# ledFire.net
KiCad netlist of a schematic drawn in EAGLE
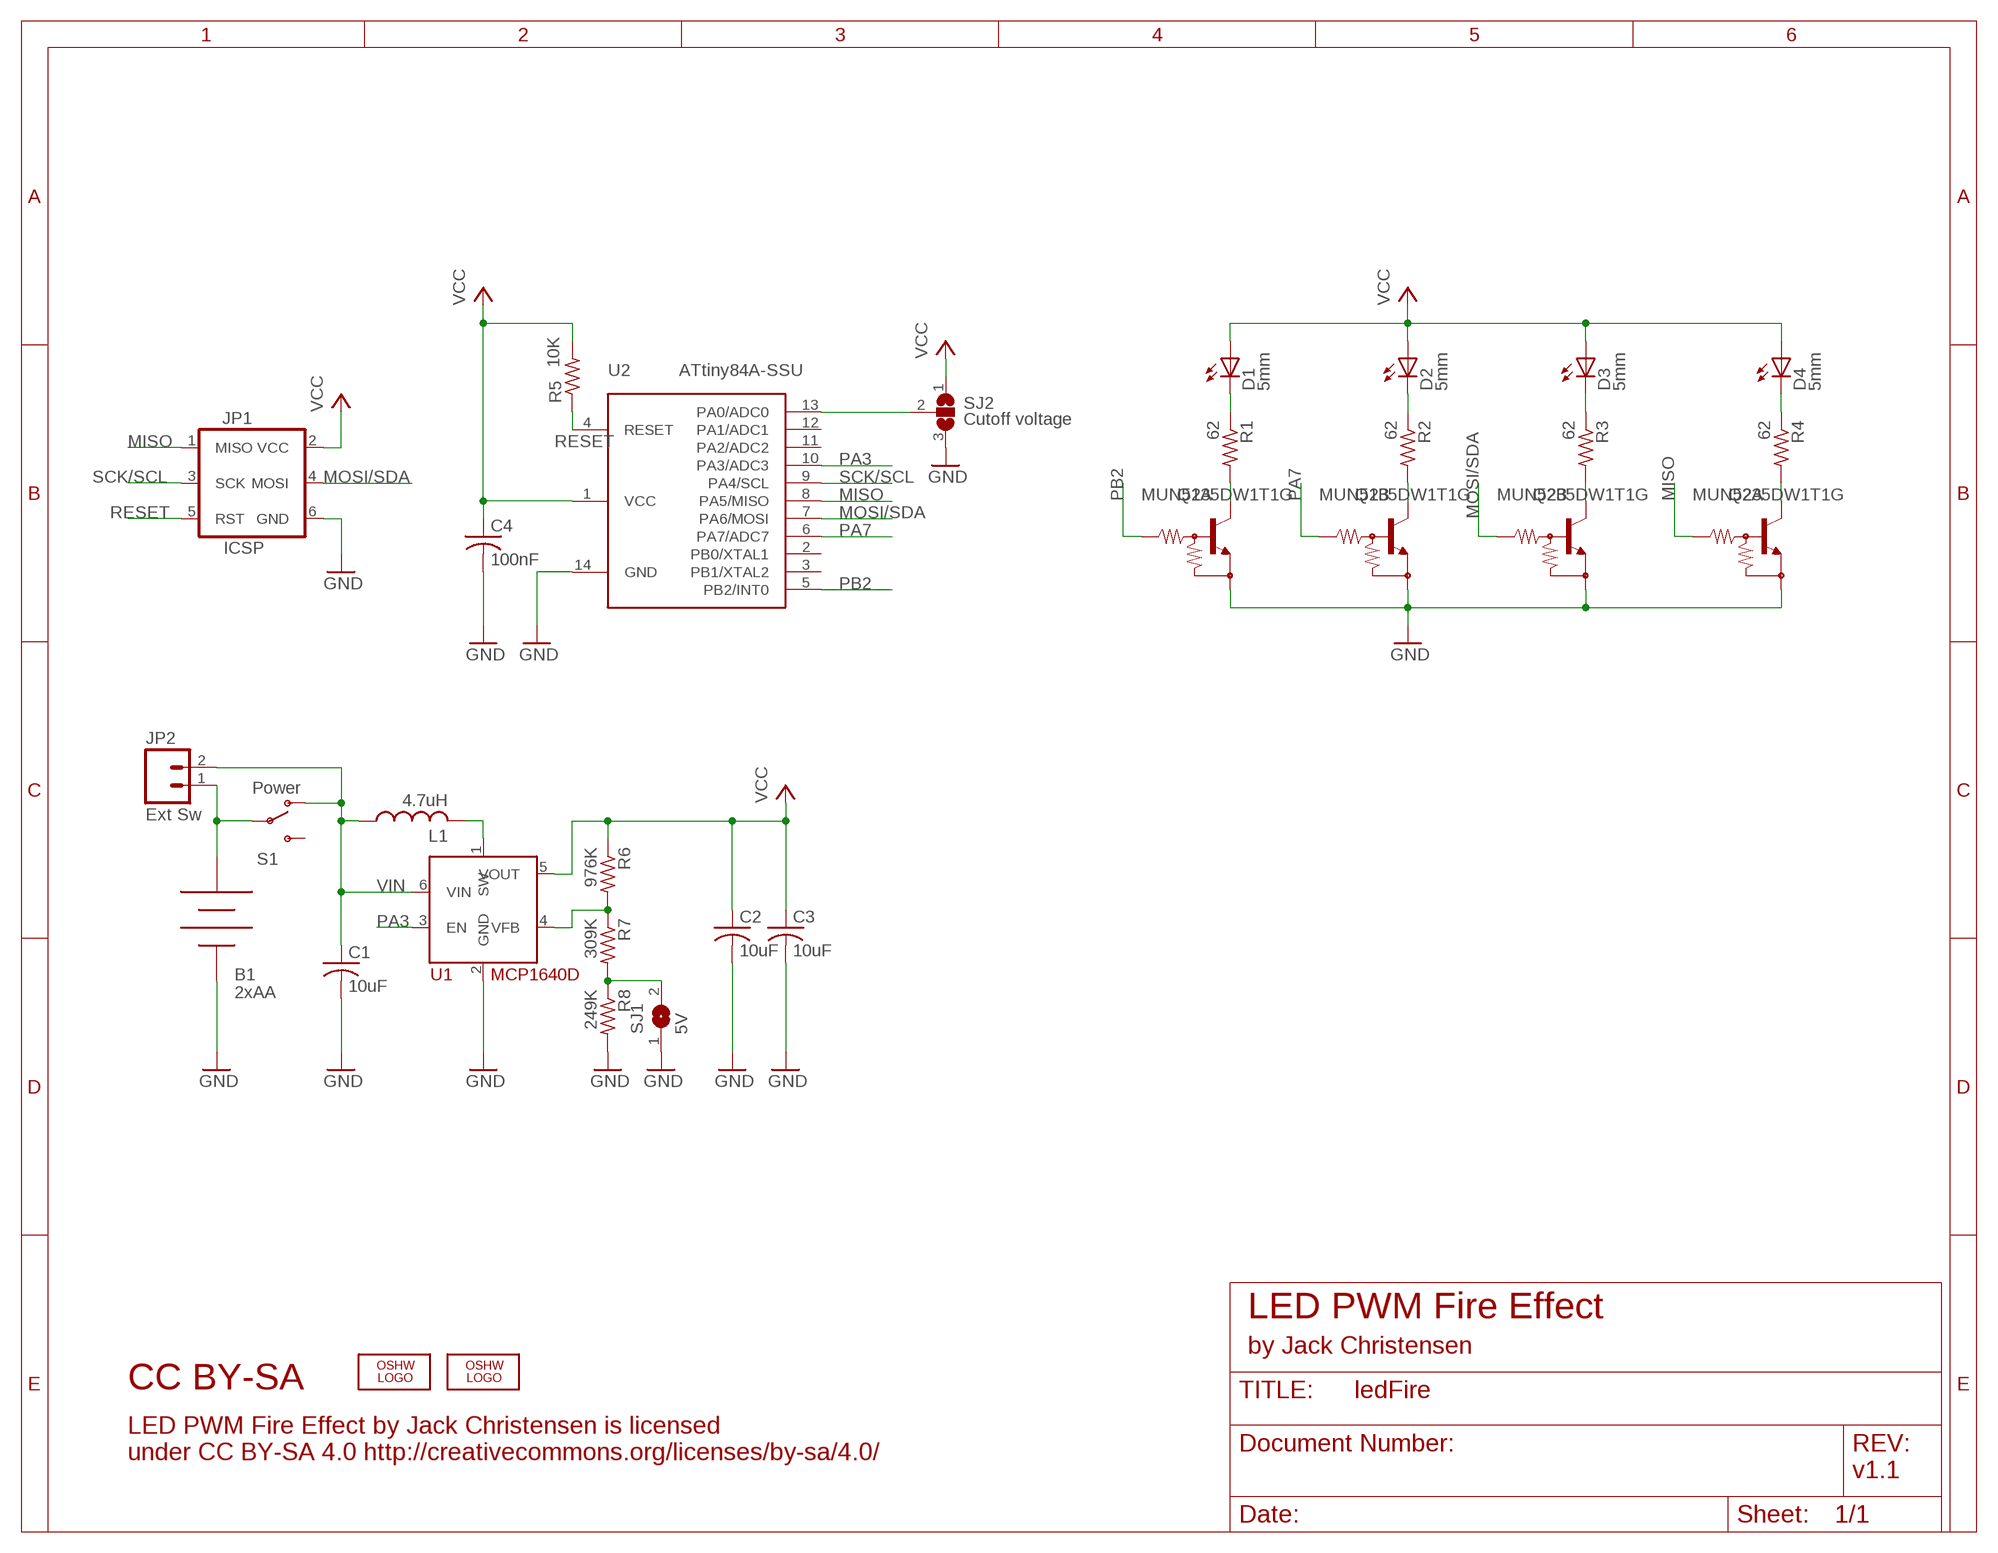
[diagram p0: schematic, sheet 1]

(export (version "E")
  (design (tool "Eeschema 10.0.6"))
  (components
    (comp (ref "B1")
      (value "2xAA")
      (footprint "eagle-import:KEYSTONE-2462-NO-HOLES")
      (libsource (lib "eagle-import") (part "BATTERY-2AANOHOLES"))
    )
    (comp (ref "C1")
      (value "10uF")
      (footprint "eagle-import:M0805")
      (libsource (lib "eagle-import") (part "C-USM0805"))
    )
    (comp (ref "C2")
      (value "10uF")
      (footprint "eagle-import:M0805")
      (libsource (lib "eagle-import") (part "C-USM0805"))
    )
    (comp (ref "C3")
      (value "10uF")
      (footprint "eagle-import:M0805")
      (libsource (lib "eagle-import") (part "C-USM0805"))
    )
    (comp (ref "C4")
      (value "100nF")
      (footprint "eagle-import:M0805")
      (libsource (lib "eagle-import") (part "C-USM0805"))
    )
    (comp (ref "D1")
      (value "5mm")
      (footprint "eagle-import:LED5MM")
      (libsource (lib "eagle-import") (part "LED5MM"))
    )
    (comp (ref "D2")
      (value "5mm")
      (footprint "eagle-import:LED5MM")
      (libsource (lib "eagle-import") (part "LED5MM"))
    )
    (comp (ref "D3")
      (value "5mm")
      (footprint "eagle-import:LED5MM")
      (libsource (lib "eagle-import") (part "LED5MM"))
    )
    (comp (ref "D4")
      (value "5mm")
      (footprint "eagle-import:LED5MM")
      (libsource (lib "eagle-import") (part "LED5MM"))
    )
    (comp (ref "JP1")
      (value "ICSP")
      (footprint "eagle-import:2X3_LOCK")
      (libsource (lib "eagle-import") (part "AVR_SPI_PRG_62X3_LOCK"))
    )
    (comp (ref "JP2")
      (value "Ext Sw")
      (footprint "eagle-import:1X02_LONGPADS")
      (libsource (lib "eagle-import") (part "M02"))
    )
    (comp (ref "L1")
      (value "4.7uH")
      (footprint "eagle-import:NRS5020")
      (libsource (lib "eagle-import") (part "INDUCTORNRS5020"))
    )
    (comp (ref "LOGO1")
      (value "OSHW_LOGO_8MILX0100-NT")
      (footprint "eagle-import:OSHW_8X100_NOTEXT")
      (libsource (lib "eagle-import") (part "OSHW_LOGO_8MILX0100-NT"))
    )
    (comp (ref "LOGO2")
      (value "OSHW_LOGO_8MILX0100-NT")
      (footprint "eagle-import:OSHW_8X100_NOTEXT")
      (libsource (lib "eagle-import") (part "OSHW_LOGO_8MILX0100-NT"))
    )
    (comp (ref "Q1")
      (value "MUN5235DW1T1G")
      (footprint "eagle-import:SOT363_PHILIPS")
      (libsource (lib "eagle-import") (part "MUN52XXSOT363"))
    )
    (comp (ref "Q2")
      (value "MUN5235DW1T1G")
      (footprint "eagle-import:SOT363_PHILIPS")
      (libsource (lib "eagle-import") (part "MUN52XXSOT363"))
    )
    (comp (ref "R1")
      (value "62")
      (footprint "eagle-import:M0805")
      (libsource (lib "eagle-import") (part "R-US_M0805"))
    )
    (comp (ref "R2")
      (value "62")
      (footprint "eagle-import:M0805")
      (libsource (lib "eagle-import") (part "R-US_M0805"))
    )
    (comp (ref "R3")
      (value "62")
      (footprint "eagle-import:M0805")
      (libsource (lib "eagle-import") (part "R-US_M0805"))
    )
    (comp (ref "R4")
      (value "62")
      (footprint "eagle-import:M0805")
      (libsource (lib "eagle-import") (part "R-US_M0805"))
    )
    (comp (ref "R5")
      (value "10K")
      (footprint "eagle-import:M0805")
      (libsource (lib "eagle-import") (part "R-US_M0805"))
    )
    (comp (ref "R6")
      (value "976K")
      (footprint "eagle-import:M0805")
      (libsource (lib "eagle-import") (part "R-US_M0805"))
    )
    (comp (ref "R7")
      (value "309K")
      (footprint "eagle-import:M0805")
      (libsource (lib "eagle-import") (part "R-US_M0805"))
    )
    (comp (ref "R8")
      (value "249K")
      (footprint "eagle-import:M0805")
      (libsource (lib "eagle-import") (part "R-US_M0805"))
    )
    (comp (ref "S1")
      (value "Power")
      (footprint "eagle-import:SWITCH-SPDT-SMD")
      (libsource (lib "eagle-import") (part "SWITCH-SPSTSMD2"))
    )
    (comp (ref "SJ1") (value "5V") (footprint "eagle-import:SJ") (libsource (lib "eagle-import") (part "SJ")))
    (comp (ref "SJ2")
      (value "Cutoff voltage")
      (footprint "eagle-import:SJ_2")
      (libsource (lib "eagle-import") (part "SJ2W"))
    )
    (comp (ref "U1")
      (value "MCP1640D")
      (footprint "eagle-import:SOT23-6")
      (libsource (lib "eagle-import") (part "MCP1640"))
    )
    (comp (ref "U2")
      (value "ATtiny84A-SSU")
      (footprint "eagle-import:SO14")
      (libsource (lib "eagle-import") (part "ATTINYX4SO14"))
    )
  )
  (nets
    (net (code "1") (name "/MISO") (class "Default")
      (node (ref "JP1") (pin "1") (pinfunction "MISO_1") (pintype "passive"))
      (node (ref "Q2") (pin "5") (pinfunction "B_5") (pintype "passive"))
      (node (ref "U2") (pin "8") (pinfunction "PA5/MISO_8") (pintype "bidirectional"))
    )
    (net (code "2") (name "/MOSI{slash}SDA") (class "Default")
      (node (ref "JP1") (pin "4") (pinfunction "MOSI_4") (pintype "passive"))
      (node (ref "Q2") (pin "2") (pinfunction "B_2") (pintype "passive"))
      (node (ref "U2") (pin "7") (pinfunction "PA6/MOSI_7") (pintype "bidirectional"))
    )
    (net (code "3") (name "/PA3") (class "Default")
      (node (ref "U1") (pin "3") (pinfunction "EN_3") (pintype "passive"))
      (node (ref "U2") (pin "10") (pinfunction "PA3/ADC3_10") (pintype "bidirectional"))
    )
    (net (code "4") (name "/PA7") (class "Default")
      (node (ref "Q1") (pin "2") (pinfunction "B_2") (pintype "passive"))
      (node (ref "U2") (pin "6") (pinfunction "PA7/ADC7_6") (pintype "bidirectional"))
    )
    (net (code "5") (name "/PB2") (class "Default")
      (node (ref "Q1") (pin "5") (pinfunction "B_5") (pintype "passive"))
      (node (ref "U2") (pin "5") (pinfunction "PB2/INT0_5") (pintype "bidirectional"))
    )
    (net (code "6") (name "/RESET") (class "Default")
      (node (ref "JP1") (pin "5") (pinfunction "RST_5") (pintype "passive"))
      (node (ref "R5") (pin "1") (pinfunction "1_1") (pintype "passive"))
      (node (ref "U2") (pin "4") (pinfunction "RESET_4") (pintype "bidirectional"))
    )
    (net (code "7") (name "/SCK{slash}SCL") (class "Default")
      (node (ref "JP1") (pin "3") (pinfunction "SCK_3") (pintype "passive"))
      (node (ref "U2") (pin "9") (pinfunction "PA4/SCL_9") (pintype "bidirectional"))
    )
    (net (code "8") (name "/VIN") (class "Default")
      (node (ref "C1") (pin "1") (pinfunction "1_1") (pintype "passive"))
      (node (ref "JP2") (pin "2") (pinfunction "2_2") (pintype "passive"))
      (node (ref "L1") (pin "P$1") (pinfunction "1_P$1") (pintype "passive"))
      (node (ref "S1") (pin "1") (pinfunction "O_1") (pintype "passive"))
      (node (ref "U1") (pin "6") (pinfunction "VIN_6") (pintype "passive"))
    )
    (net (code "9") (name "GND") (class "Default")
      (node (ref "B1") (pin "NEG") (pinfunction "NEG_NEG") (pintype "bidirectional"))
      (node (ref "C1") (pin "2") (pinfunction "2_2") (pintype "passive"))
      (node (ref "C2") (pin "2") (pinfunction "2_2") (pintype "passive"))
      (node (ref "C3") (pin "2") (pinfunction "2_2") (pintype "passive"))
      (node (ref "C4") (pin "2") (pinfunction "2_2") (pintype "passive"))
      (node (ref "JP1") (pin "6") (pinfunction "GND_6") (pintype "passive"))
      (node (ref "Q1") (pin "1") (pinfunction "E_1") (pintype "passive"))
      (node (ref "Q1") (pin "4") (pinfunction "E_4") (pintype "passive"))
      (node (ref "Q2") (pin "1") (pinfunction "E_1") (pintype "passive"))
      (node (ref "Q2") (pin "4") (pinfunction "E_4") (pintype "passive"))
      (node (ref "R8") (pin "2") (pinfunction "2_2") (pintype "passive"))
      (node (ref "SJ1") (pin "1") (pinfunction "1_1") (pintype "passive"))
      (node (ref "SJ2") (pin "3") (pinfunction "3_3") (pintype "passive"))
      (node (ref "U1") (pin "2") (pinfunction "GND_2") (pintype "passive"))
      (node (ref "U2") (pin "14") (pinfunction "GND_14") (pintype "bidirectional"))
    )
    (net (code "10") (name "Net-(D1-C)") (class "Default")
      (node (ref "D1") (pin "K") (pinfunction "C_K") (pintype "passive"))
      (node (ref "R1") (pin "1") (pinfunction "1_1") (pintype "passive"))
    )
    (net (code "11") (name "Net-(D2-C)") (class "Default")
      (node (ref "D2") (pin "K") (pinfunction "C_K") (pintype "passive"))
      (node (ref "R2") (pin "1") (pinfunction "1_1") (pintype "passive"))
    )
    (net (code "12") (name "Net-(D3-C)") (class "Default")
      (node (ref "D3") (pin "K") (pinfunction "C_K") (pintype "passive"))
      (node (ref "R3") (pin "1") (pinfunction "1_1") (pintype "passive"))
    )
    (net (code "13") (name "Net-(D4-C)") (class "Default")
      (node (ref "D4") (pin "K") (pinfunction "C_K") (pintype "passive"))
      (node (ref "R4") (pin "1") (pinfunction "1_1") (pintype "passive"))
    )
    (net (code "14") (name "Net-(L1-2)") (class "Default")
      (node (ref "L1") (pin "P$2") (pinfunction "2_P$2") (pintype "passive"))
      (node (ref "U1") (pin "1") (pinfunction "SW_1") (pintype "passive"))
    )
    (net (code "15") (name "Net-(Q1A-C)") (class "Default")
      (node (ref "Q1") (pin "3") (pinfunction "C_3") (pintype "passive"))
      (node (ref "R1") (pin "2") (pinfunction "2_2") (pintype "passive"))
    )
    (net (code "16") (name "Net-(Q1B-C)") (class "Default")
      (node (ref "Q1") (pin "6") (pinfunction "C_6") (pintype "passive"))
      (node (ref "R2") (pin "2") (pinfunction "2_2") (pintype "passive"))
    )
    (net (code "17") (name "Net-(Q2A-C)") (class "Default")
      (node (ref "Q2") (pin "3") (pinfunction "C_3") (pintype "passive"))
      (node (ref "R4") (pin "2") (pinfunction "2_2") (pintype "passive"))
    )
    (net (code "18") (name "Net-(Q2B-C)") (class "Default")
      (node (ref "Q2") (pin "6") (pinfunction "C_6") (pintype "passive"))
      (node (ref "R3") (pin "2") (pinfunction "2_2") (pintype "passive"))
    )
    (net (code "19") (name "Net-(R7-Pad2)") (class "Default")
      (node (ref "R7") (pin "2") (pinfunction "2_2") (pintype "passive"))
      (node (ref "R8") (pin "1") (pinfunction "1_1") (pintype "passive"))
      (node (ref "SJ1") (pin "2") (pinfunction "2_2") (pintype "passive"))
    )
    (net (code "20") (name "Net-(S1-P)") (class "Default")
      (node (ref "B1") (pin "POS") (pinfunction "POS_POS") (pintype "bidirectional"))
      (node (ref "JP2") (pin "1") (pinfunction "1_1") (pintype "passive"))
      (node (ref "S1") (pin "2") (pinfunction "P_2") (pintype "passive"))
    )
    (net (code "21") (name "Net-(U1-VFB)") (class "Default")
      (node (ref "R6") (pin "2") (pinfunction "2_2") (pintype "passive"))
      (node (ref "R7") (pin "1") (pinfunction "1_1") (pintype "passive"))
      (node (ref "U1") (pin "4") (pinfunction "VFB_4") (pintype "passive"))
    )
    (net (code "22") (name "Net-(U2-PA0{slash}ADC0)") (class "Default")
      (node (ref "SJ2") (pin "2") (pinfunction "2_2") (pintype "passive"))
      (node (ref "U2") (pin "13") (pinfunction "PA0/ADC0_13") (pintype "bidirectional"))
    )
    (net (code "23") (name "VCC") (class "Default")
      (node (ref "C2") (pin "1") (pinfunction "1_1") (pintype "passive"))
      (node (ref "C3") (pin "1") (pinfunction "1_1") (pintype "passive"))
      (node (ref "C4") (pin "1") (pinfunction "1_1") (pintype "passive"))
      (node (ref "D1") (pin "A") (pinfunction "A_A") (pintype "passive"))
      (node (ref "D2") (pin "A") (pinfunction "A_A") (pintype "passive"))
      (node (ref "D3") (pin "A") (pinfunction "A_A") (pintype "passive"))
      (node (ref "D4") (pin "A") (pinfunction "A_A") (pintype "passive"))
      (node (ref "JP1") (pin "2") (pinfunction "VCC_2") (pintype "passive"))
      (node (ref "R5") (pin "2") (pinfunction "2_2") (pintype "passive"))
      (node (ref "R6") (pin "1") (pinfunction "1_1") (pintype "passive"))
      (node (ref "SJ2") (pin "1") (pinfunction "1_1") (pintype "passive"))
      (node (ref "U1") (pin "5") (pinfunction "VOUT_5") (pintype "passive"))
      (node (ref "U2") (pin "1") (pinfunction "VCC_1") (pintype "bidirectional"))
    )
    (net (code "24") (name "unconnected-(S1-S-Pad3)") (class "Default")
      (node (ref "S1") (pin "3") (pinfunction "S_3") (pintype "passive"))
    )
    (net (code "25") (name "unconnected-(U2-PA1{slash}ADC1-Pad12)") (class "Default")
      (node (ref "U2") (pin "12") (pinfunction "PA1/ADC1_12") (pintype "bidirectional"))
    )
    (net (code "26") (name "unconnected-(U2-PA2{slash}ADC2-Pad11)") (class "Default")
      (node (ref "U2") (pin "11") (pinfunction "PA2/ADC2_11") (pintype "bidirectional"))
    )
    (net (code "27") (name "unconnected-(U2-PB0{slash}XTAL1-Pad2)") (class "Default")
      (node (ref "U2") (pin "2") (pinfunction "PB0/XTAL1_2") (pintype "bidirectional"))
    )
    (net (code "28") (name "unconnected-(U2-PB1{slash}XTAL2-Pad3)") (class "Default")
      (node (ref "U2") (pin "3") (pinfunction "PB1/XTAL2_3") (pintype "bidirectional"))
    )
  )
)
